# Sensirion_connector_board_v002.net
KiCad netlist of a schematic drawn in EAGLE
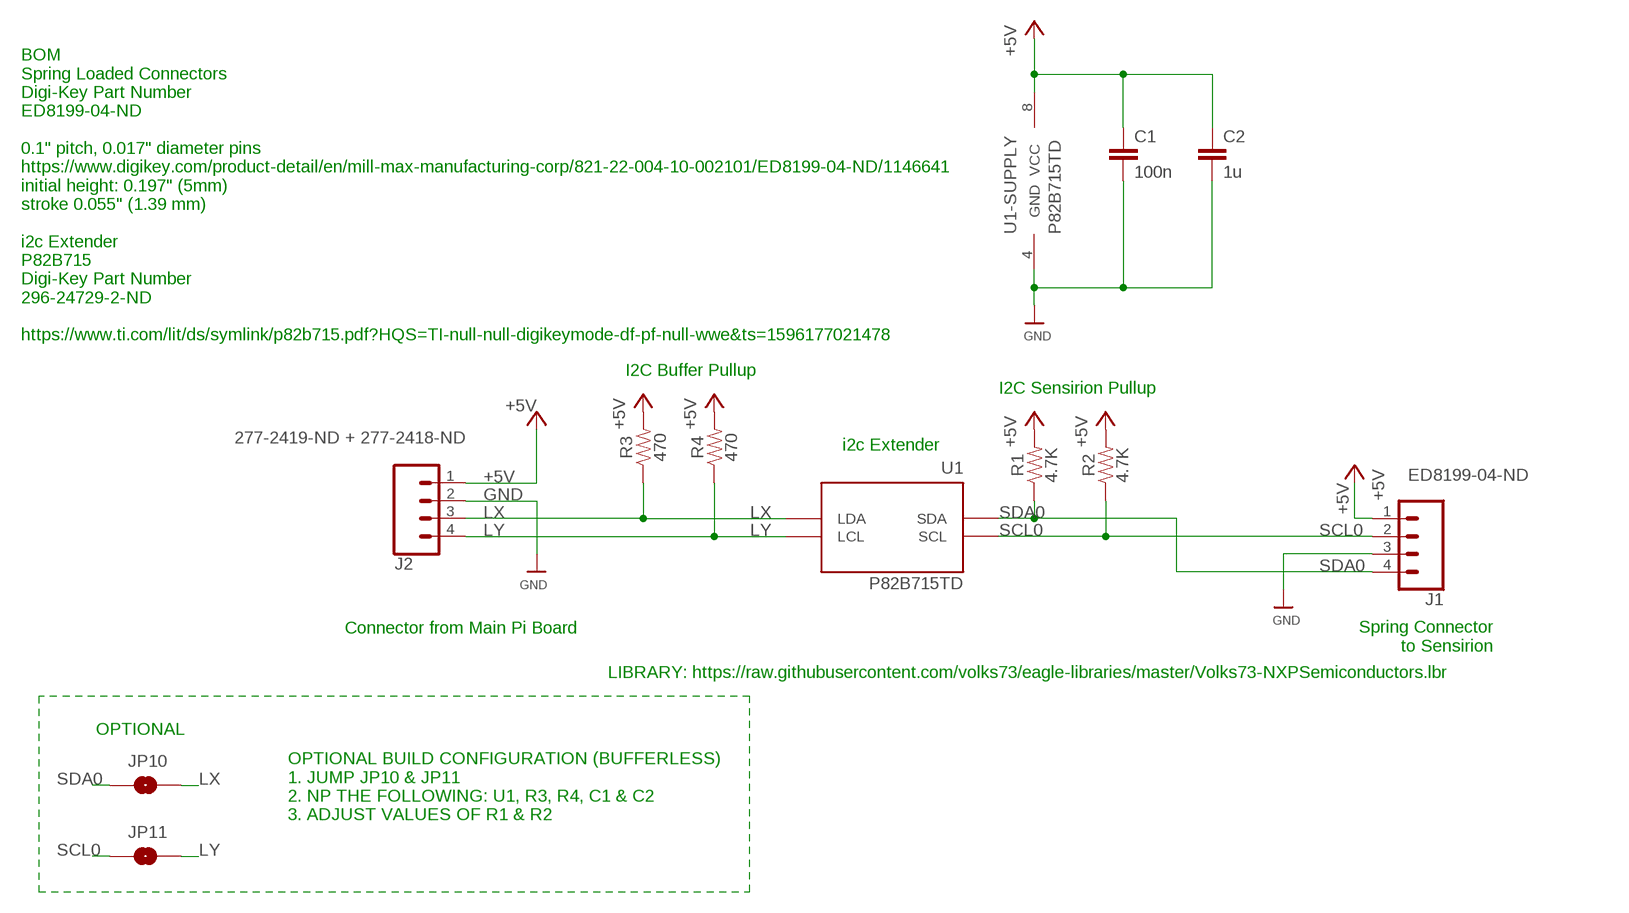
[diagram p0: schematic, sheet 1]

(export (version "E")
  (design (tool "Eeschema 10.0.6"))
  (components
    (comp (ref "C1")
      (value "100n")
      (footprint "eagle-import:0805")
      (libsource (lib "eagle-import") (part "CAP-0805"))
    )
    (comp (ref "C2")
      (value "1u")
      (footprint "eagle-import:0805")
      (libsource (lib "eagle-import") (part "CAP-0805"))
    )
    (comp (ref "J1")
      (value "ED8199-04-ND")
      (footprint "eagle-import:1X04_30MILL_DIA")
      (libsource (lib "eagle-import") (part "CONN_0430MILL_DIA"))
    )
    (comp (ref "J2")
      (value "277-2419-ND + 277-2418-ND")
      (footprint "eagle-import:1X04_3.5MM_RA")
      (libsource (lib "eagle-import") (part "CONN_043.5MM_RA"))
    )
    (comp (ref "JP10")
      (value "JUMPER-SMT_2_NO_SILK")
      (footprint "eagle-import:SMT-JUMPER_2_NO_SILK")
      (libsource (lib "eagle-import") (part "JUMPER-SMT_2_NO_SILK"))
    )
    (comp (ref "JP11")
      (value "JUMPER-SMT_2_NO_SILK")
      (footprint "eagle-import:SMT-JUMPER_2_NO_SILK")
      (libsource (lib "eagle-import") (part "JUMPER-SMT_2_NO_SILK"))
    )
    (comp (ref "R1")
      (value "4.7K")
      (footprint "eagle-import:0805")
      (libsource (lib "eagle-import") (part "0.3OHM-0805-1/8W-1%"))
    )
    (comp (ref "R2")
      (value "4.7K")
      (footprint "eagle-import:0805")
      (libsource (lib "eagle-import") (part "0.3OHM-0805-1/8W-1%"))
    )
    (comp (ref "R3")
      (value "470")
      (footprint "eagle-import:0805")
      (libsource (lib "eagle-import") (part "0.3OHM-0805-1/8W-1%"))
    )
    (comp (ref "R4")
      (value "470")
      (footprint "eagle-import:0805")
      (libsource (lib "eagle-import") (part "0.3OHM-0805-1/8W-1%"))
    )
    (comp (ref "U1")
      (value "P82B715TD")
      (footprint "eagle-import:SOIC-8")
      (fields (field (name "MANUFACTURER") "NXP Semiconductors") (field (name "PART_NUMBER") "P82B715TD,118"))
      (libsource (lib "eagle-import") (part "P82B715?TD"))
    )
  )
  (nets
    (net (code "1") (name "+5V") (class "Default")
      (node (ref "C1") (pin "1") (pinfunction "1_1") (pintype "passive"))
      (node (ref "C2") (pin "1") (pinfunction "1_1") (pintype "passive"))
      (node (ref "J1") (pin "1") (pinfunction "1_1") (pintype "passive"))
      (node (ref "J2") (pin "1") (pinfunction "1_1") (pintype "passive"))
      (node (ref "R1") (pin "2") (pinfunction "2_2") (pintype "passive"))
      (node (ref "R2") (pin "2") (pinfunction "2_2") (pintype "passive"))
      (node (ref "R3") (pin "2") (pinfunction "2_2") (pintype "passive"))
      (node (ref "R4") (pin "2") (pinfunction "2_2") (pintype "passive"))
      (node (ref "U1") (pin "8") (pinfunction "VCC_8") (pintype "bidirectional"))
    )
    (net (code "2") (name "/LX") (class "Default")
      (node (ref "J2") (pin "3") (pinfunction "3_3") (pintype "passive"))
      (node (ref "JP10") (pin "2") (pinfunction "2_2") (pintype "passive"))
      (node (ref "R3") (pin "1") (pinfunction "1_1") (pintype "passive"))
      (node (ref "U1") (pin "7") (pinfunction "LDA_7") (pintype "bidirectional"))
    )
    (net (code "3") (name "/LY") (class "Default")
      (node (ref "J2") (pin "4") (pinfunction "4_4") (pintype "passive"))
      (node (ref "JP11") (pin "2") (pinfunction "2_2") (pintype "passive"))
      (node (ref "R4") (pin "1") (pinfunction "1_1") (pintype "passive"))
      (node (ref "U1") (pin "2") (pinfunction "LCL_2") (pintype "bidirectional"))
    )
    (net (code "4") (name "/SCL0") (class "Default")
      (node (ref "J1") (pin "2") (pinfunction "2_2") (pintype "passive"))
      (node (ref "JP11") (pin "1") (pinfunction "1_1") (pintype "passive"))
      (node (ref "R2") (pin "1") (pinfunction "1_1") (pintype "passive"))
      (node (ref "U1") (pin "3") (pinfunction "SCL_3") (pintype "bidirectional"))
    )
    (net (code "5") (name "/SDA0") (class "Default")
      (node (ref "J1") (pin "4") (pinfunction "4_4") (pintype "passive"))
      (node (ref "JP10") (pin "1") (pinfunction "1_1") (pintype "passive"))
      (node (ref "R1") (pin "1") (pinfunction "1_1") (pintype "passive"))
      (node (ref "U1") (pin "6") (pinfunction "SDA_6") (pintype "bidirectional"))
    )
    (net (code "6") (name "GND") (class "Default")
      (node (ref "C1") (pin "2") (pinfunction "2_2") (pintype "passive"))
      (node (ref "C2") (pin "2") (pinfunction "2_2") (pintype "passive"))
      (node (ref "J1") (pin "3") (pinfunction "3_3") (pintype "passive"))
      (node (ref "J2") (pin "2") (pinfunction "2_2") (pintype "passive"))
      (node (ref "U1") (pin "4") (pinfunction "GND_4") (pintype "bidirectional"))
    )
  )
)
